# ENC28J60.net
KiCad netlist of a schematic drawn in Altium Designer
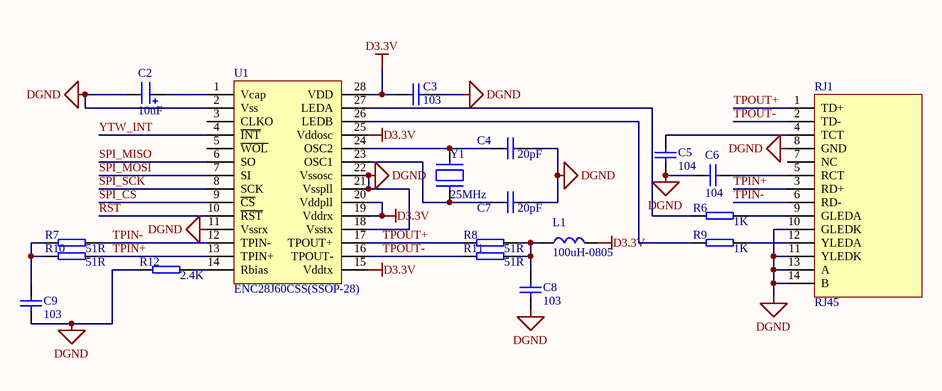
[diagram p0: ENC28J60.SchDoc]

(export (version "E")
  (design (tool "Eeschema 10.0.6"))
  (components
    (comp (ref "C2")
      (value "10uF")
      (footprint "13*20")
      (description "直插电解电容")
      (libsource (lib "常用元件") (part "Cap_pol"))
    )
    (comp (ref "C3")
      (value "103")
      (footprint "0603C")
      (description "贴片电容")
      (libsource (lib "常用元件") (part "Cap"))
    )
    (comp (ref "C4")
      (value "20pF")
      (footprint "0603C")
      (description "贴片电容")
      (libsource (lib "常用元件") (part "Cap"))
    )
    (comp (ref "C5")
      (value "104")
      (footprint "0603C")
      (description "贴片电容")
      (libsource (lib "常用元件") (part "Cap"))
    )
    (comp (ref "C6")
      (value "104")
      (footprint "0603C")
      (description "贴片电容")
      (libsource (lib "常用元件") (part "Cap"))
    )
    (comp (ref "C7")
      (value "20pF")
      (footprint "0603C")
      (description "贴片电容")
      (libsource (lib "常用元件") (part "Cap"))
    )
    (comp (ref "C8")
      (value "103")
      (footprint "0603C")
      (description "贴片电容")
      (libsource (lib "常用元件") (part "Cap"))
    )
    (comp (ref "C9")
      (value "103")
      (footprint "0603C")
      (description "贴片电容")
      (libsource (lib "常用元件") (part "Cap"))
    )
    (comp (ref "L1") (value "100uH-0805") (footprint "0603P") (libsource (lib "常用元件") (part "L")))
    (comp (ref "R6") (value "1K") (footprint "0402R") (libsource (lib "常用元件") (part "RES-10K")))
    (comp (ref "R7") (value "51R") (footprint "0402R") (libsource (lib "常用元件") (part "RES-10K")))
    (comp (ref "R8") (value "51R") (footprint "0402R") (libsource (lib "常用元件") (part "RES-10K")))
    (comp (ref "R9") (value "1K") (footprint "0402R") (libsource (lib "常用元件") (part "RES-10K")))
    (comp (ref "R10") (value "51R") (footprint "0402R") (libsource (lib "常用元件") (part "RES-10K")))
    (comp (ref "R11") (value "51R") (footprint "0402R") (libsource (lib "常用元件") (part "RES-10K")))
    (comp (ref "R12") (value "2.4K") (footprint "0402R") (libsource (lib "常用元件") (part "RES-10K")))
    (comp (ref "RJ1") (value "RJ45") (description "网络变压器") (libsource (lib "常用元件") (part "RJ45")))
    (comp (ref "U1")
      (value "ENC28J60CSS(SSOP-28)")
      (footprint "ENC28J60-SSOP28_5.3MM")
      (description "10M以太网芯片")
      (libsource (lib "常用元件") (part "ENC28J60CSS(SSOP-28)"))
    )
    (comp (ref "Y1")
      (value "25MHz")
      (footprint "XTAL")
      (description "8M")
      (libsource (lib "常用元件") (part "XTAL"))
    )
  )
  (nets
    (net (code "1") (name "/RST") (class "Default")
      (node (ref "U1") (pin "10") (pinfunction "~{RST}_10") (pintype "passive"))
    )
    (net (code "2") (name "/SPI_CS") (class "Default")
      (node (ref "U1") (pin "9") (pinfunction "~{CS}_9") (pintype "passive"))
    )
    (net (code "3") (name "/SPI_MISO") (class "Default")
      (node (ref "U1") (pin "6") (pinfunction "SO_6") (pintype "passive"))
    )
    (net (code "4") (name "/SPI_MOSI") (class "Default")
      (node (ref "U1") (pin "7") (pinfunction "SI_7") (pintype "passive"))
    )
    (net (code "5") (name "/SPI_SCK") (class "Default")
      (node (ref "U1") (pin "8") (pinfunction "SCK_8") (pintype "passive"))
    )
    (net (code "6") (name "/TPIN+") (class "Default")
      (node (ref "R10") (pin "2") (pinfunction "2_2") (pintype "passive"))
      (node (ref "RJ1") (pin "3") (pinfunction "RD+_3") (pintype "passive"))
      (node (ref "U1") (pin "13") (pinfunction "TPIN+_13") (pintype "passive"))
    )
    (net (code "7") (name "/TPIN-") (class "Default")
      (node (ref "R7") (pin "2") (pinfunction "2_2") (pintype "passive"))
      (node (ref "RJ1") (pin "6") (pinfunction "RD-_6") (pintype "passive"))
      (node (ref "U1") (pin "12") (pinfunction "TPIN-_12") (pintype "passive"))
    )
    (net (code "8") (name "/TPOUT+") (class "Default")
      (node (ref "R8") (pin "1") (pinfunction "1_1") (pintype "passive"))
      (node (ref "RJ1") (pin "1") (pinfunction "TD+_1") (pintype "passive"))
      (node (ref "U1") (pin "17") (pinfunction "TPOUT+_17") (pintype "passive"))
    )
    (net (code "9") (name "/TPOUT-") (class "Default")
      (node (ref "R11") (pin "1") (pinfunction "1_1") (pintype "passive"))
      (node (ref "RJ1") (pin "2") (pinfunction "TD-_2") (pintype "passive"))
      (node (ref "U1") (pin "16") (pinfunction "TPOUT-_16") (pintype "passive"))
    )
    (net (code "10") (name "/YTW_INT") (class "Default")
      (node (ref "U1") (pin "4") (pinfunction "~{INT}_4") (pintype "passive"))
    )
    (net (code "11") (name "D3.3V") (class "Default")
      (node (ref "C3") (pin "1") (pinfunction "1_1") (pintype "passive"))
      (node (ref "L1") (pin "2") (pintype "passive"))
      (node (ref "U1") (pin "15") (pinfunction "Vddtx_15") (pintype "passive"))
      (node (ref "U1") (pin "19") (pinfunction "Vddrx_19") (pintype "passive"))
      (node (ref "U1") (pin "20") (pinfunction "Vddpll_20") (pintype "passive"))
      (node (ref "U1") (pin "25") (pinfunction "Vddosc_25") (pintype "passive"))
      (node (ref "U1") (pin "28") (pinfunction "VDD_28") (pintype "passive"))
    )
    (net (code "12") (name "DGND") (class "Default")
      (node (ref "C2") (pin "2") (pinfunction "2_2") (pintype "passive"))
      (node (ref "C3") (pin "2") (pinfunction "2_2") (pintype "passive"))
      (node (ref "C4") (pin "2") (pinfunction "2_2") (pintype "passive"))
      (node (ref "C5") (pin "1") (pinfunction "1_1") (pintype "passive"))
      (node (ref "C6") (pin "1") (pinfunction "1_1") (pintype "passive"))
      (node (ref "C7") (pin "2") (pinfunction "2_2") (pintype "passive"))
      (node (ref "C8") (pin "1") (pinfunction "1_1") (pintype "passive"))
      (node (ref "C9") (pin "1") (pinfunction "1_1") (pintype "passive"))
      (node (ref "R12") (pin "1") (pinfunction "1_1") (pintype "passive"))
      (node (ref "RJ1") (pin "10") (pinfunction "GLEDK_10") (pintype "passive"))
      (node (ref "RJ1") (pin "11") (pinfunction "YLEDK_11") (pintype "passive"))
      (node (ref "RJ1") (pin "13") (pinfunction "A_13") (pintype "passive"))
      (node (ref "RJ1") (pin "14") (pinfunction "B_14") (pintype "passive"))
      (node (ref "RJ1") (pin "8") (pinfunction "GND_8") (pintype "passive"))
      (node (ref "U1") (pin "11") (pinfunction "Vssrx_11") (pintype "passive"))
      (node (ref "U1") (pin "18") (pinfunction "Vsstx_18") (pintype "passive"))
      (node (ref "U1") (pin "2") (pinfunction "Vss_2") (pintype "passive"))
      (node (ref "U1") (pin "21") (pinfunction "Vsspll_21") (pintype "passive"))
      (node (ref "U1") (pin "22") (pinfunction "Vssosc_22") (pintype "passive"))
    )
    (net (code "13") (name "Net-(C8-Pad2)") (class "Default")
      (node (ref "C8") (pin "2") (pinfunction "2_2") (pintype "passive"))
      (node (ref "L1") (pin "1") (pintype "passive"))
      (node (ref "R11") (pin "2") (pinfunction "2_2") (pintype "passive"))
      (node (ref "R8") (pin "2") (pinfunction "2_2") (pintype "passive"))
    )
    (net (code "14") (name "Net-(C9-Pad2)") (class "Default")
      (node (ref "C9") (pin "2") (pinfunction "2_2") (pintype "passive"))
      (node (ref "R10") (pin "1") (pinfunction "1_1") (pintype "passive"))
      (node (ref "R7") (pin "1") (pinfunction "1_1") (pintype "passive"))
    )
    (net (code "15") (name "Net-(RJ1-GLEDA)") (class "Default")
      (node (ref "R6") (pin "2") (pinfunction "2_2") (pintype "passive"))
      (node (ref "RJ1") (pin "9") (pinfunction "GLEDA_9") (pintype "passive"))
    )
    (net (code "16") (name "Net-(RJ1-RCT)") (class "Default")
      (node (ref "C6") (pin "2") (pinfunction "2_2") (pintype "passive"))
      (node (ref "RJ1") (pin "5") (pinfunction "RCT_5") (pintype "passive"))
    )
    (net (code "17") (name "Net-(RJ1-TCT)") (class "Default")
      (node (ref "C5") (pin "2") (pinfunction "2_2") (pintype "passive"))
      (node (ref "RJ1") (pin "4") (pinfunction "TCT_4") (pintype "passive"))
    )
    (net (code "18") (name "Net-(RJ1-YLEDA)") (class "Default")
      (node (ref "R9") (pin "2") (pinfunction "2_2") (pintype "passive"))
      (node (ref "RJ1") (pin "12") (pinfunction "YLEDA_12") (pintype "passive"))
    )
    (net (code "19") (name "Net-(U1-LEDA)") (class "Default")
      (node (ref "R6") (pin "1") (pinfunction "1_1") (pintype "passive"))
      (node (ref "U1") (pin "27") (pinfunction "LEDA_27") (pintype "passive"))
    )
    (net (code "20") (name "Net-(U1-LEDB)") (class "Default")
      (node (ref "R9") (pin "1") (pinfunction "1_1") (pintype "passive"))
      (node (ref "U1") (pin "26") (pinfunction "LEDB_26") (pintype "passive"))
    )
    (net (code "21") (name "Net-(U1-OSC1)") (class "Default")
      (node (ref "C7") (pin "1") (pinfunction "1_1") (pintype "passive"))
      (node (ref "U1") (pin "23") (pinfunction "OSC1_23") (pintype "passive"))
      (node (ref "Y1") (pin "1") (pinfunction "1_1") (pintype "passive"))
    )
    (net (code "22") (name "Net-(U1-OSC2)") (class "Default")
      (node (ref "C4") (pin "1") (pinfunction "1_1") (pintype "passive"))
      (node (ref "U1") (pin "24") (pinfunction "OSC2_24") (pintype "passive"))
      (node (ref "Y1") (pin "2") (pinfunction "2_2") (pintype "passive"))
    )
    (net (code "23") (name "Net-(U1-Rbias)") (class "Default")
      (node (ref "R12") (pin "2") (pinfunction "2_2") (pintype "passive"))
      (node (ref "U1") (pin "14") (pinfunction "Rbias_14") (pintype "passive"))
    )
    (net (code "24") (name "Net-(U1-Vcap)") (class "Default")
      (node (ref "C2") (pin "1") (pinfunction "1_1") (pintype "passive"))
      (node (ref "U1") (pin "1") (pinfunction "Vcap_1") (pintype "passive"))
    )
    (net (code "25") (name "unconnected-(RJ1-NC-Pad7)") (class "Default")
      (node (ref "RJ1") (pin "7") (pinfunction "NC_7") (pintype "passive"))
    )
    (net (code "26") (name "unconnected-(U1-CLKO-Pad3)") (class "Default")
      (node (ref "U1") (pin "3") (pinfunction "CLKO_3") (pintype "passive"))
    )
    (net (code "27") (name "unconnected-(U1-~{WOL}-Pad5)") (class "Default")
      (node (ref "U1") (pin "5") (pinfunction "~{WOL}_5") (pintype "passive"))
    )
  )
)
